# HT7560.net
KiCad netlist of a schematic drawn in Altium Designer
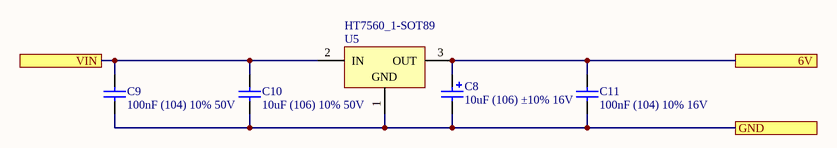
[diagram p0: HT7560.SchDoc]

(export (version "E")
  (design (tool "Eeschema 10.0.6"))
  (components
    (comp (ref "C8")
      (value "10uF (106) ±10% 16V")
      (footprint "CASE-A_3216")
      (description "钽电容")
      (libsource (lib "Miscellaneous Devices LC") (part "3216 10uF (106) 10% 16V"))
    )
    (comp (ref "C9")
      (value "100nF (104) 10% 50V")
      (footprint "0603_C")
      (description "贴片电容")
      (libsource (lib "Miscellaneous Devices LC") (part "0603 100nF (104) 10% 50V"))
    )
    (comp (ref "C10")
      (value "10uF (106) 10% 50V")
      (footprint "1206_C")
      (description "贴片电容")
      (libsource (lib "Miscellaneous Devices LC") (part "1206 10uF (106) 10% 50V"))
    )
    (comp (ref "C11")
      (value "100nF (104) 10% 16V")
      (footprint "0402_C")
      (description "贴片电容")
      (libsource (lib "Miscellaneous Devices LC") (part "0402 100nF (104) 10% 16V"))
    )
    (comp (ref "U5")
      (value "HT7560_1-SOT89")
      (footprint "SOT89_N")
      (description "100mA Low Power LDO, Output Voltage 6.0V, SOT89 Pkg")
      (libsource (lib "Holtek Semiconductor Power Management") (part "HT7560_1-SOT89"))
    )
  )
  (nets
    (net (code "1") (name "/6V") (class "Default")
      (node (ref "C11") (pin "1") (pinfunction "1_1") (pintype "passive"))
      (node (ref "C8") (pin "1") (pinfunction "1_1") (pintype "passive"))
      (node (ref "U5") (pin "3") (pinfunction "OUT_3") (pintype "power_in"))
    )
    (net (code "2") (name "/GND") (class "Default")
      (node (ref "C10") (pin "2") (pinfunction "2_2") (pintype "passive"))
      (node (ref "C11") (pin "2") (pinfunction "2_2") (pintype "passive"))
      (node (ref "C8") (pin "2") (pinfunction "2_2") (pintype "passive"))
      (node (ref "C9") (pin "1") (pinfunction "1_1") (pintype "passive"))
      (node (ref "U5") (pin "1") (pinfunction "GND_1") (pintype "power_in"))
    )
    (net (code "3") (name "/VIN") (class "Default")
      (node (ref "C10") (pin "1") (pinfunction "1_1") (pintype "passive"))
      (node (ref "C9") (pin "2") (pinfunction "2_2") (pintype "passive"))
      (node (ref "U5") (pin "2") (pinfunction "IN_2") (pintype "power_in"))
    )
  )
)
